# POWR0008_BCR_System.net
KiCad netlist of a schematic drawn in Altium Designer
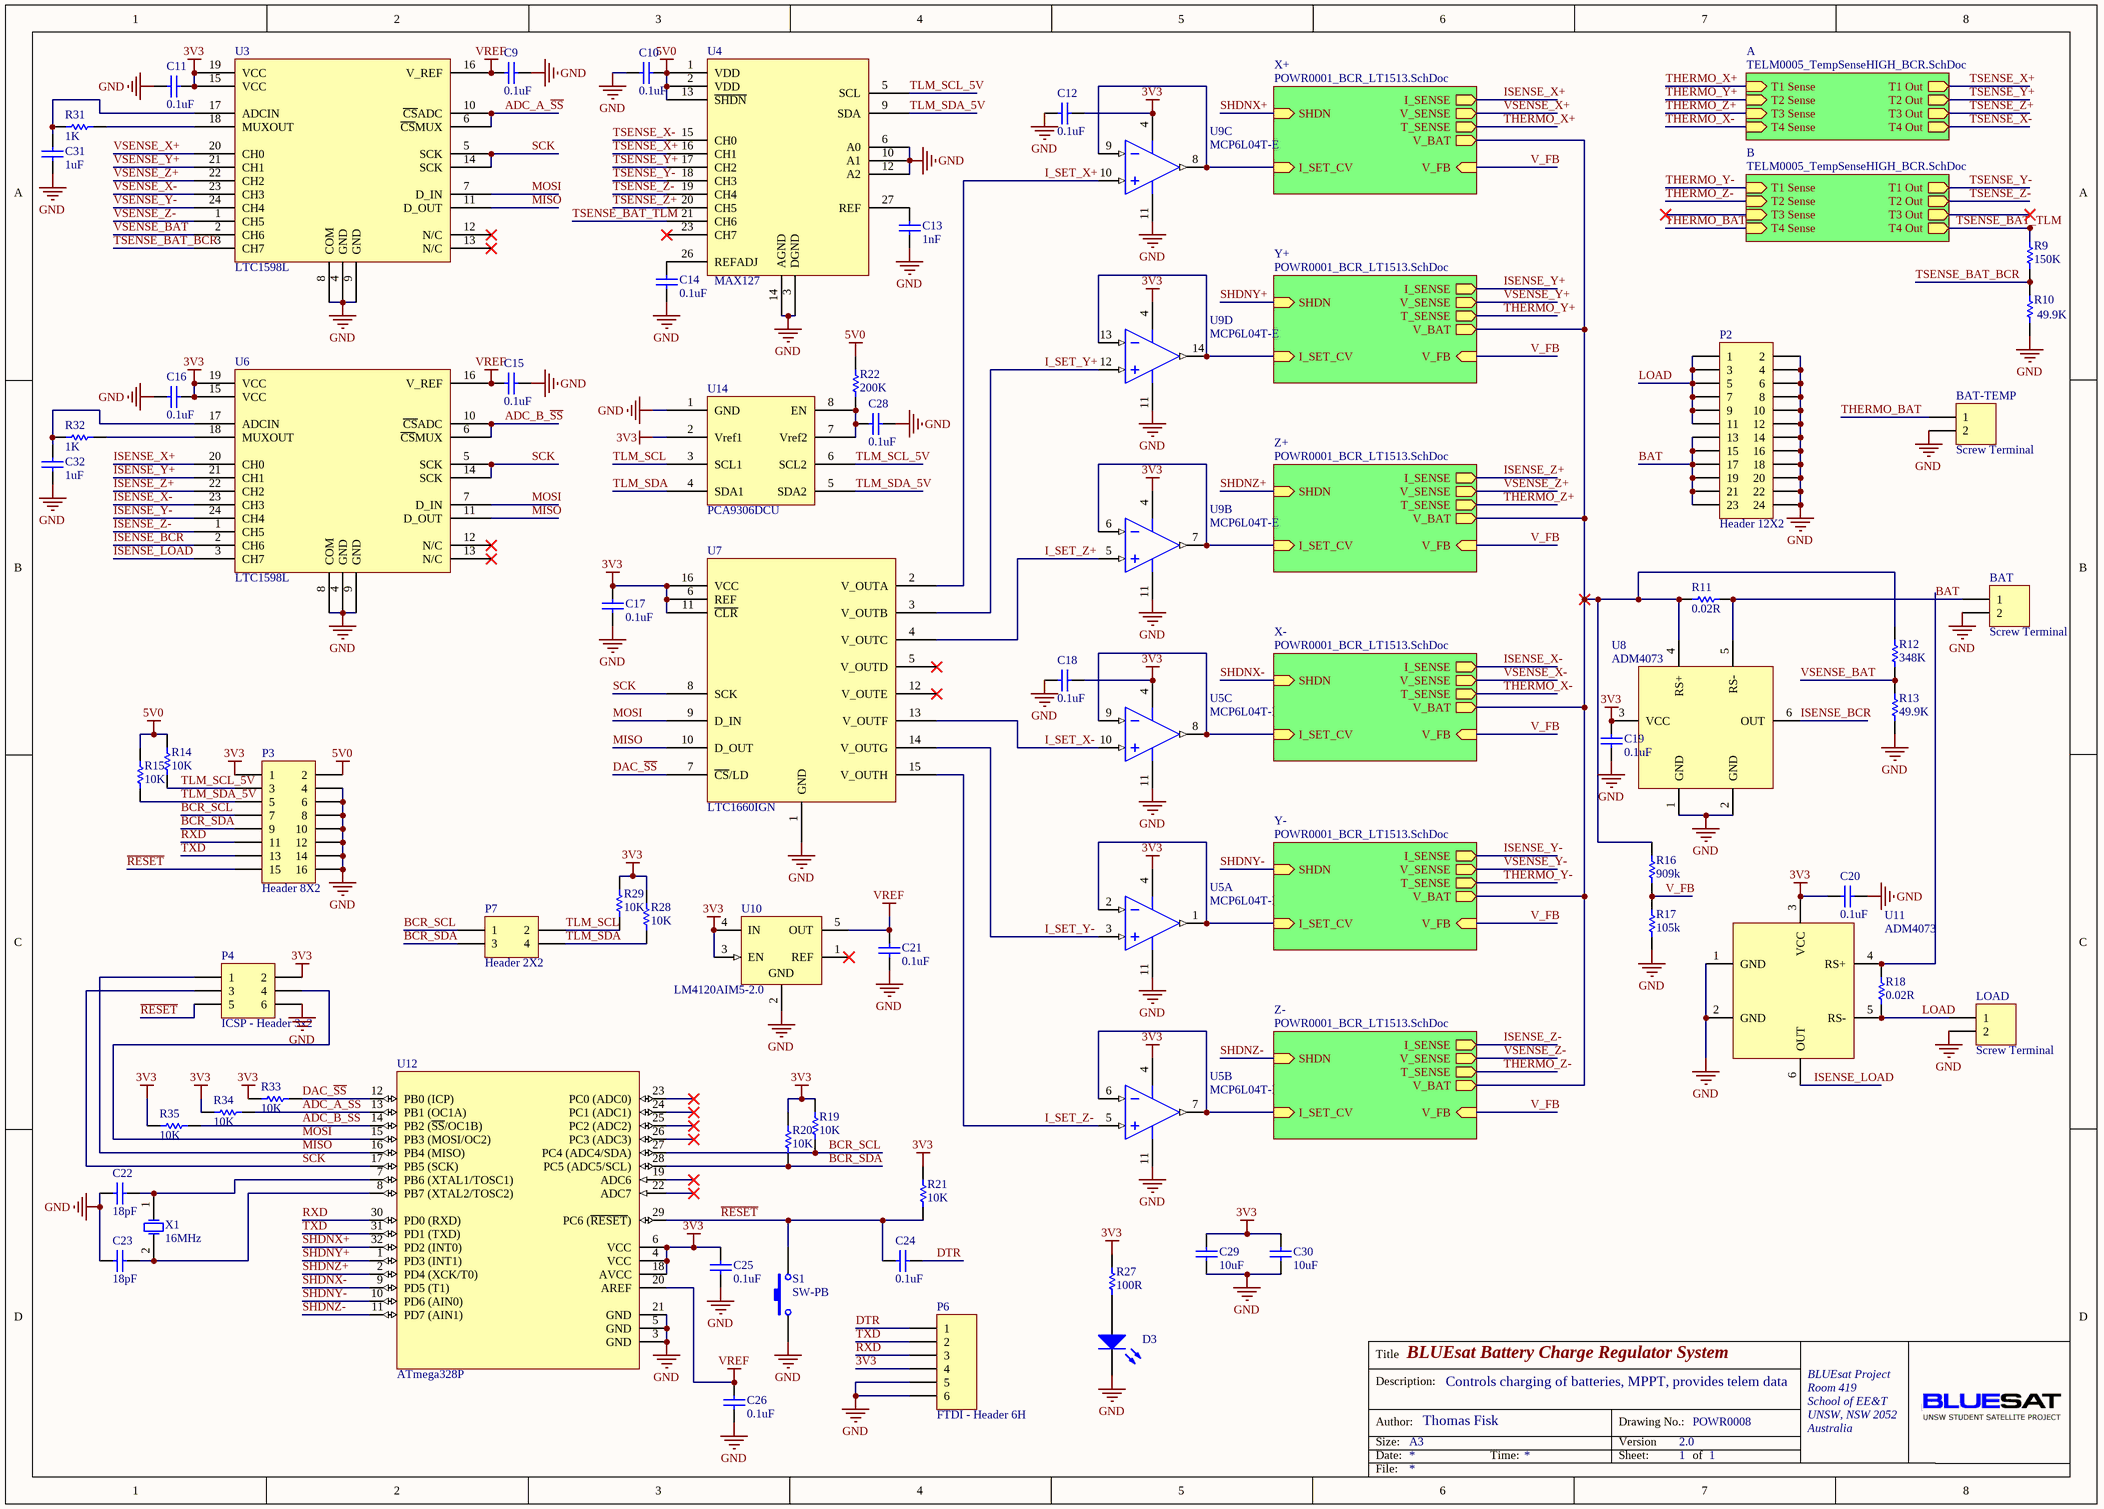
[diagram p0: POWR0008_BCR_System.SchDoc]

(export (version "E")
  (design (tool "Eeschema 10.0.6"))
  (components
    (comp (ref "BAT")
      (value "Screw Terminal")
      (footprint "5.05mm Terminal Block - 2")
      (description "Header, 2-Pin")
      (fields (field (name "PUBLISHER") "Altium Limited"))
      (libsource (lib "Miscellaneous Connectors") (part "Header 2"))
    )
    (comp (ref "BAT-TEMP")
      (value "Screw Terminal")
      (footprint "5.05mm Terminal Block - 2")
      (description "Header, 2-Pin")
      (fields (field (name "PUBLISHER") "Altium Limited"))
      (libsource (lib "Miscellaneous Connectors") (part "Header 2"))
    )
    (comp (ref "C9")
      (value "0.1uF")
      (footprint "CAPC2012M")
      (description "Capacitor")
      (fields (field (name "Comment") "Cap") (field (name "PUBLISHER") "Altium Limited"))
      (libsource (lib "Miscellaneous Devices") (part "Cap"))
    )
    (comp (ref "C10")
      (value "0.1uF")
      (footprint "CAPC2012M")
      (description "Capacitor")
      (fields (field (name "Comment") "Cap") (field (name "PUBLISHER") "Altium Limited"))
      (libsource (lib "Miscellaneous Devices") (part "Cap"))
    )
    (comp (ref "C11")
      (value "0.1uF")
      (footprint "CAPC2012M")
      (description "Capacitor")
      (fields (field (name "Comment") "Cap") (field (name "PUBLISHER") "Altium Limited"))
      (libsource (lib "Miscellaneous Devices") (part "Cap"))
    )
    (comp (ref "C12")
      (value "0.1uF")
      (footprint "CAPC2012M")
      (description "Capacitor")
      (fields (field (name "Comment") "Cap") (field (name "PUBLISHER") "Altium Limited"))
      (libsource (lib "Miscellaneous Devices") (part "Cap"))
    )
    (comp (ref "C13")
      (value "1nF")
      (footprint "CAPC2012M")
      (description "Capacitor")
      (fields (field (name "Comment") "Cap") (field (name "PUBLISHER") "Altium Limited"))
      (libsource (lib "Miscellaneous Devices") (part "Cap"))
    )
    (comp (ref "C14")
      (value "0.1uF")
      (footprint "CAPC2012M")
      (description "Capacitor")
      (fields (field (name "Comment") "Cap") (field (name "PUBLISHER") "Altium Limited"))
      (libsource (lib "Miscellaneous Devices") (part "Cap"))
    )
    (comp (ref "C15")
      (value "0.1uF")
      (footprint "CAPC2012M")
      (description "Capacitor")
      (fields (field (name "Comment") "Cap") (field (name "PUBLISHER") "Altium Limited"))
      (libsource (lib "Miscellaneous Devices") (part "Cap"))
    )
    (comp (ref "C16")
      (value "0.1uF")
      (footprint "CAPC2012M")
      (description "Capacitor")
      (fields (field (name "Comment") "Cap") (field (name "PUBLISHER") "Altium Limited"))
      (libsource (lib "Miscellaneous Devices") (part "Cap"))
    )
    (comp (ref "C17")
      (value "0.1uF")
      (footprint "CAPC2012M")
      (description "Capacitor")
      (fields (field (name "Comment") "Cap") (field (name "PUBLISHER") "Altium Limited"))
      (libsource (lib "Miscellaneous Devices") (part "Cap"))
    )
    (comp (ref "C18")
      (value "0.1uF")
      (footprint "CAPC2012M")
      (description "Capacitor")
      (fields (field (name "Comment") "Cap") (field (name "PUBLISHER") "Altium Limited"))
      (libsource (lib "Miscellaneous Devices") (part "Cap"))
    )
    (comp (ref "C19")
      (value "0.1uF")
      (footprint "CAPC2012M")
      (description "Capacitor")
      (fields (field (name "Comment") "Cap") (field (name "PUBLISHER") "Altium Limited"))
      (libsource (lib "Miscellaneous Devices") (part "Cap"))
    )
    (comp (ref "C20")
      (value "0.1uF")
      (footprint "CAPC2012M")
      (description "Capacitor")
      (fields (field (name "Comment") "Cap") (field (name "PUBLISHER") "Altium Limited"))
      (libsource (lib "Miscellaneous Devices") (part "Cap"))
    )
    (comp (ref "C21")
      (value "0.1uF")
      (footprint "CAPC2012M")
      (description "Capacitor")
      (fields (field (name "Comment") "Cap") (field (name "PUBLISHER") "Altium Limited"))
      (libsource (lib "Miscellaneous Devices") (part "Cap"))
    )
    (comp (ref "C22")
      (value "18pF")
      (footprint "CAPC2012M")
      (description "Capacitor")
      (fields (field (name "Comment") "Cap") (field (name "PUBLISHER") "Altium Limited"))
      (libsource (lib "Miscellaneous Devices") (part "Cap"))
    )
    (comp (ref "C23")
      (value "18pF")
      (footprint "CAPC2012M")
      (description "Capacitor")
      (fields (field (name "Comment") "Cap") (field (name "PUBLISHER") "Altium Limited"))
      (libsource (lib "Miscellaneous Devices") (part "Cap"))
    )
    (comp (ref "C24")
      (value "0.1uF")
      (footprint "CAPC2012M")
      (description "Capacitor")
      (fields (field (name "Comment") "Cap") (field (name "PUBLISHER") "Altium Limited"))
      (libsource (lib "Miscellaneous Devices") (part "Cap"))
    )
    (comp (ref "C25")
      (value "0.1uF")
      (footprint "CAPC2012M")
      (description "Capacitor")
      (fields (field (name "Comment") "Cap") (field (name "PUBLISHER") "Altium Limited"))
      (libsource (lib "Miscellaneous Devices") (part "Cap"))
    )
    (comp (ref "C26")
      (value "0.1uF")
      (footprint "CAPC2012M")
      (description "Capacitor")
      (fields (field (name "Comment") "Cap") (field (name "PUBLISHER") "Altium Limited"))
      (libsource (lib "Miscellaneous Devices") (part "Cap"))
    )
    (comp (ref "C28")
      (value "0.1uF")
      (footprint "CAPC2012M")
      (description "Capacitor")
      (fields (field (name "Comment") "Cap") (field (name "PUBLISHER") "Altium Limited"))
      (libsource (lib "Miscellaneous Devices") (part "Cap"))
    )
    (comp (ref "C29")
      (value "10uF")
      (footprint "CAPC3216M")
      (description "Capacitor")
      (fields (field (name "Comment") "Cap") (field (name "PUBLISHER") "Altium Limited"))
      (libsource (lib "Miscellaneous Devices") (part "Cap"))
    )
    (comp (ref "C30")
      (value "10uF")
      (footprint "CAPC3216M")
      (description "Capacitor")
      (fields (field (name "Comment") "Cap") (field (name "PUBLISHER") "Altium Limited"))
      (libsource (lib "Miscellaneous Devices") (part "Cap"))
    )
    (comp (ref "C31")
      (value "1uF")
      (footprint "CAPC2012M")
      (description "Capacitor")
      (fields (field (name "Comment") "Cap") (field (name "PUBLISHER") "Altium Limited"))
      (libsource (lib "Miscellaneous Devices") (part "Cap"))
    )
    (comp (ref "C32")
      (value "1uF")
      (footprint "CAPC2012M")
      (description "Capacitor")
      (fields (field (name "Comment") "Cap") (field (name "PUBLISHER") "Altium Limited"))
      (libsource (lib "Miscellaneous Devices") (part "Cap"))
    )
    (comp (ref "D3")
      (value "0805 LED")
      (footprint "CD2012-0805")
      (description "Typical RED, GREEN, YELLOW, AMBER GaAs LED")
      (fields (field (name "PUBLISHER") "Altium Limited"))
      (libsource (lib "Miscellaneous Devices") (part "LED2"))
    )
    (comp (ref "LOAD")
      (value "Screw Terminal")
      (footprint "5.05mm Terminal Block - 2")
      (description "Header, 2-Pin")
      (fields (field (name "PUBLISHER") "Altium Limited"))
      (libsource (lib "Miscellaneous Connectors") (part "Header 2"))
    )
    (comp (ref "P2")
      (value "Header 12X2")
      (footprint "HDR2X12")
      (description "Header, 12-Pin, Dual row")
      (fields (field (name "PUBLISHER") "Altium Limited"))
      (libsource (lib "Miscellaneous Connectors") (part "Header 12X2"))
    )
    (comp (ref "P3")
      (value "Header 8X2")
      (footprint "HDR2X8")
      (description "Header, 8-Pin, Dual row")
      (fields (field (name "PUBLISHER") "Altium Limited"))
      (libsource (lib "Miscellaneous Connectors") (part "Header 8X2"))
    )
    (comp (ref "P4")
      (value "ICSP - Header 3x2")
      (footprint "HDR2X3")
      (description "Header, 3-Pin, Dual row")
      (fields (field (name "PUBLISHER") "Altium Limited"))
      (libsource (lib "Miscellaneous Connectors") (part "Header 3X2"))
    )
    (comp (ref "P6")
      (value "FTDI - Header 6H")
      (footprint "HDR1X6H")
      (description "Header, 6-Pin, Right Angle")
      (fields (field (name "PUBLISHER") "Altium Limited"))
      (libsource (lib "Miscellaneous Connectors") (part "Header 6H"))
    )
    (comp (ref "P7")
      (value "Header 2X2")
      (footprint "HDR2X2")
      (description "Header, 2-Pin, Dual row")
      (fields (field (name "PUBLISHER") "Altium Limited"))
      (libsource (lib "Miscellaneous Connectors") (part "Header 2X2"))
    )
    (comp (ref "R9")
      (value "150K")
      (footprint "RESC2012M")
      (description "Resistor")
      (fields (field (name "Comment") "Res1") (field (name "PUBLISHER") "Altium Limited"))
      (libsource (lib "Miscellaneous Devices") (part "Res1"))
    )
    (comp (ref "R10")
      (value "49.9K")
      (footprint "RESC2012M")
      (description "Resistor")
      (fields (field (name "Comment") "Res1") (field (name "PUBLISHER") "Altium Limited"))
      (libsource (lib "Miscellaneous Devices") (part "Res1"))
    )
    (comp (ref "R11")
      (value "0.02R")
      (footprint "RESC2012M")
      (description "Resistor")
      (fields (field (name "Comment") "0805 Resistor") (field (name "PUBLISHER") "Altium Limited"))
      (libsource (lib "Miscellaneous Devices") (part "Res1"))
    )
    (comp (ref "R12")
      (value "348K")
      (footprint "RESC2012M")
      (description "Resistor")
      (fields (field (name "Comment") "Res1") (field (name "PUBLISHER") "Altium Limited"))
      (libsource (lib "Miscellaneous Devices") (part "Res1"))
    )
    (comp (ref "R13")
      (value "49.9K")
      (footprint "RESC2012M")
      (description "Resistor")
      (fields (field (name "Comment") "Res1") (field (name "PUBLISHER") "Altium Limited"))
      (libsource (lib "Miscellaneous Devices") (part "Res1"))
    )
    (comp (ref "R14")
      (value "10K")
      (footprint "RESC2012M")
      (description "Resistor")
      (fields (field (name "Comment") "Res1") (field (name "PUBLISHER") "Altium Limited"))
      (libsource (lib "Miscellaneous Devices") (part "Res1"))
    )
    (comp (ref "R15")
      (value "10K")
      (footprint "RESC2012M")
      (description "Resistor")
      (fields (field (name "Comment") "Res1") (field (name "PUBLISHER") "Altium Limited"))
      (libsource (lib "Miscellaneous Devices") (part "Res1"))
    )
    (comp (ref "R16")
      (value "909k")
      (footprint "RESC2012M")
      (description "Resistor")
      (fields (field (name "Comment") "Res1") (field (name "PUBLISHER") "Altium Limited"))
      (libsource (lib "Miscellaneous Devices") (part "Res1"))
    )
    (comp (ref "R17")
      (value "105k")
      (footprint "RESC2012M")
      (description "Resistor")
      (fields (field (name "Comment") "Res1") (field (name "PUBLISHER") "Altium Limited"))
      (libsource (lib "Miscellaneous Devices") (part "Res1"))
    )
    (comp (ref "R18")
      (value "0.02R")
      (footprint "RESC2012M")
      (description "Resistor")
      (fields (field (name "Comment") "0805 Resistor") (field (name "PUBLISHER") "Altium Limited"))
      (libsource (lib "Miscellaneous Devices") (part "Res1"))
    )
    (comp (ref "R19")
      (value "10K")
      (footprint "RESC2012M")
      (description "Resistor")
      (fields (field (name "Comment") "Res1") (field (name "PUBLISHER") "Altium Limited"))
      (libsource (lib "Miscellaneous Devices") (part "Res1"))
    )
    (comp (ref "R20")
      (value "10K")
      (footprint "RESC2012M")
      (description "Resistor")
      (fields (field (name "Comment") "Res1") (field (name "PUBLISHER") "Altium Limited"))
      (libsource (lib "Miscellaneous Devices") (part "Res1"))
    )
    (comp (ref "R21")
      (value "10K")
      (footprint "RESC2012M")
      (description "Resistor")
      (fields (field (name "Comment") "Res1") (field (name "PUBLISHER") "Altium Limited"))
      (libsource (lib "Miscellaneous Devices") (part "Res1"))
    )
    (comp (ref "R22")
      (value "200K")
      (footprint "RESC2012M")
      (description "Resistor")
      (fields (field (name "Comment") "Res1") (field (name "PUBLISHER") "Altium Limited"))
      (libsource (lib "Miscellaneous Devices") (part "Res1"))
    )
    (comp (ref "R27")
      (value "100R")
      (footprint "RESC2012M")
      (description "Resistor")
      (fields (field (name "Comment") "Res1") (field (name "PUBLISHER") "Altium Limited"))
      (libsource (lib "Miscellaneous Devices") (part "Res1"))
    )
    (comp (ref "R28")
      (value "10K")
      (footprint "RESC2012M")
      (description "Resistor")
      (fields (field (name "Comment") "Res1") (field (name "PUBLISHER") "Altium Limited"))
      (libsource (lib "Miscellaneous Devices") (part "Res1"))
    )
    (comp (ref "R29")
      (value "10K")
      (footprint "RESC2012M")
      (description "Resistor")
      (fields (field (name "Comment") "Res1") (field (name "PUBLISHER") "Altium Limited"))
      (libsource (lib "Miscellaneous Devices") (part "Res1"))
    )
    (comp (ref "R31")
      (value "1K")
      (footprint "RESC2012M")
      (description "Resistor")
      (fields (field (name "Comment") "Res1") (field (name "PUBLISHER") "Altium Limited"))
      (libsource (lib "Miscellaneous Devices") (part "Res1"))
    )
    (comp (ref "R32")
      (value "1K")
      (footprint "RESC2012M")
      (description "Resistor")
      (fields (field (name "Comment") "Res1") (field (name "PUBLISHER") "Altium Limited"))
      (libsource (lib "Miscellaneous Devices") (part "Res1"))
    )
    (comp (ref "R33")
      (value "10K")
      (footprint "RESC2012M")
      (description "Resistor")
      (fields (field (name "Comment") "Res1") (field (name "PUBLISHER") "Altium Limited"))
      (libsource (lib "Miscellaneous Devices") (part "Res1"))
    )
    (comp (ref "R34")
      (value "10K")
      (footprint "RESC2012M")
      (description "Resistor")
      (fields (field (name "Comment") "Res1") (field (name "PUBLISHER") "Altium Limited"))
      (libsource (lib "Miscellaneous Devices") (part "Res1"))
    )
    (comp (ref "R35")
      (value "10K")
      (footprint "RESC2012M")
      (description "Resistor")
      (fields (field (name "Comment") "Res1") (field (name "PUBLISHER") "Altium Limited"))
      (libsource (lib "Miscellaneous Devices") (part "Res1"))
    )
    (comp (ref "S1")
      (value "SW-PB")
      (footprint "RESET SWITCH")
      (description "Switch")
      (fields (field (name "PUBLISHER") "Altium Limited"))
      (libsource (lib "Miscellaneous Devices") (part "SW-PB"))
    )
    (comp (ref "U3") (value "LTC1598L") (footprint "LTC1598L") (libsource (lib "BCR") (part "LTC1598L")))
    (comp (ref "U4")
      (value "MAX127")
      (footprint "SSOP28 - MAX127")
      (description "8 Channel, 12 bit, I2C DAS")
      (libsource (lib "Schlib1") (part "MAX127"))
    )
    (comp (ref "U5")
      (value "MCP6L04T-E")
      (footprint "MTC14_N")
      (description "3 MHz, Micropower RRO Amplifier")
      (fields
        (field (name "PARTNUMBER") "LMV554MT")
        (field (name "MANUFACTURER") "National Semiconductor")
        (field (name "PUBLISHER") "Altium Limited")
      )
      (libsource (lib "NSC Amplifier") (part "LMV554MT"))
    )
    (comp (ref "U6") (value "LTC1598L") (footprint "LTC1598L") (libsource (lib "BCR") (part "LTC1598L")))
    (comp (ref "U7") (value "LTC1660IGN") (footprint "LTC1660") (libsource (lib "BCR") (part "LTC1660IGN")))
    (comp (ref "U8")
      (value "ADM4073")
      (footprint "SOT95P285X145-6N")
      (description "Current Sense Amplifer")
      (libsource (lib "Schlib1") (part "ADM4073"))
    )
    (comp (ref "U9")
      (value "MCP6L04T-E")
      (footprint "MTC14_N")
      (description "3 MHz, Micropower RRO Amplifier")
      (fields
        (field (name "PARTNUMBER") "LMV554MT")
        (field (name "MANUFACTURER") "National Semiconductor")
        (field (name "PUBLISHER") "Altium Limited")
      )
      (libsource (lib "NSC Amplifier") (part "LMV554MT"))
    )
    (comp (ref "U10")
      (value "LM4120AIM5-2.0")
      (footprint "MF05A_N")
      (description "Precision Micropower Low Dropout Voltage Reference")
      (fields
        (field (name "MANUFACTURER") "National Semiconductor")
        (field (name "DIGIKEYPARTNUMBER") "LM4120AIM5-2.0CT-ND")
        (field (name "PUBLISHER") "Altium Limited")
      )
      (libsource (lib "NSC Voltage Reference") (part "LM4120AIM5-2.0"))
    )
    (comp (ref "U11")
      (value "ADM4073")
      (footprint "SOT95P285X145-6N")
      (description "Current Sense Amplifer")
      (libsource (lib "") (part "ADM4073_1"))
    )
    (comp (ref "U12")
      (value "ATmega328P")
      (footprint "32A_N")
      (description "8-Bit AVR Microcontroller with 8K Bytes of In-System Programmable Flash Memory")
      (fields (field (name "PUBLISHER") "Altium Limited"))
      (libsource (lib "Atmel Microcontroller 8-Bit AVR") (part "ATmega8-16AC"))
    )
    (comp (ref "U14")
      (value "PCA9306DCU")
      (footprint "TSSOP50P310X90-8N")
      (libsource (lib "BCR") (part "PCA9306"))
    )
    (comp (ref "X1")
      (value "16MHz")
      (footprint "HC49 - No border")
      (description "Crystal Oscillator")
      (fields (field (name "PUBLISHER") "Altium Limited"))
      (libsource (lib "ECS Crystal Oscillator") (part "ECS-110-S-5P"))
    )
  )
  (nets
    (net (code "1") (name "/ADC_A_~{SS}") (class "Default")
      (node (ref "R34") (pin "2") (pinfunction "2_2") (pintype "passive"))
      (node (ref "U12") (pin "13") (pinfunction "PB1_(OC1A)_13") (pintype "bidirectional"))
      (node (ref "U3") (pin "10") (pinfunction "~{CS}ADC_10") (pintype "passive"))
      (node (ref "U3") (pin "6") (pinfunction "~{CS}MUX_6") (pintype "passive"))
    )
    (net (code "2") (name "/ADC_B_~{SS}") (class "Default")
      (node (ref "R35") (pin "2") (pinfunction "2_2") (pintype "passive"))
      (node (ref "U12") (pin "14") (pinfunction "PB2_(~{SS}/OC1B)_14") (pintype "bidirectional"))
      (node (ref "U6") (pin "10") (pinfunction "~{CS}ADC_10") (pintype "passive"))
      (node (ref "U6") (pin "6") (pinfunction "~{CS}MUX_6") (pintype "passive"))
    )
    (net (code "3") (name "/BAT") (class "Default")
      (node (ref "BAT") (pin "1") (pinfunction "1_1") (pintype "passive"))
      (node (ref "P2") (pin "13") (pinfunction "13_13") (pintype "passive"))
      (node (ref "P2") (pin "15") (pinfunction "15_15") (pintype "passive"))
      (node (ref "P2") (pin "17") (pinfunction "17_17") (pintype "passive"))
      (node (ref "P2") (pin "19") (pinfunction "19_19") (pintype "passive"))
      (node (ref "P2") (pin "21") (pinfunction "21_21") (pintype "passive"))
      (node (ref "P2") (pin "23") (pinfunction "23_23") (pintype "passive"))
      (node (ref "R11") (pin "2") (pinfunction "2_2") (pintype "passive"))
      (node (ref "R18") (pin "2") (pinfunction "2_2") (pintype "passive"))
      (node (ref "U11") (pin "4") (pinfunction "RS+_4") (pintype "passive"))
      (node (ref "U8") (pin "5") (pinfunction "RS-_5") (pintype "passive"))
    )
    (net (code "4") (name "/BCR_SCL") (class "Default")
      (node (ref "P3") (pin "7") (pinfunction "7_7") (pintype "passive"))
      (node (ref "P7") (pin "1") (pinfunction "1_1") (pintype "passive"))
      (node (ref "R19") (pin "2") (pinfunction "2_2") (pintype "passive"))
      (node (ref "U12") (pin "27") (pinfunction "PC4_(ADC4/SDA)_27") (pintype "bidirectional"))
    )
    (net (code "5") (name "/BCR_SDA") (class "Default")
      (node (ref "P3") (pin "9") (pinfunction "9_9") (pintype "passive"))
      (node (ref "P7") (pin "3") (pinfunction "3_3") (pintype "passive"))
      (node (ref "R20") (pin "2") (pinfunction "2_2") (pintype "passive"))
      (node (ref "U12") (pin "28") (pinfunction "PC5_(ADC5/SCL)_28") (pintype "bidirectional"))
    )
    (net (code "6") (name "/DAC_~{SS}") (class "Default")
      (node (ref "R33") (pin "2") (pinfunction "2_2") (pintype "passive"))
      (node (ref "U12") (pin "12") (pinfunction "PB0_(ICP)_12") (pintype "bidirectional"))
      (node (ref "U7") (pin "7") (pinfunction "~{CS}/LD_7") (pintype "passive"))
    )
    (net (code "7") (name "/DTR") (class "Default")
      (node (ref "C24") (pin "1") (pinfunction "1_1") (pintype "passive"))
      (node (ref "P6") (pin "1") (pinfunction "1_1") (pintype "passive"))
    )
    (net (code "8") (name "/ISENSE_BCR") (class "Default")
      (node (ref "U6") (pin "2") (pinfunction "CH6_2") (pintype "passive"))
      (node (ref "U8") (pin "6") (pinfunction "OUT_6") (pintype "passive"))
    )
    (net (code "9") (name "/ISENSE_LOAD") (class "Default")
      (node (ref "U11") (pin "6") (pinfunction "OUT_6") (pintype "passive"))
      (node (ref "U6") (pin "3") (pinfunction "CH7_3") (pintype "passive"))
    )
    (net (code "10") (name "/ISENSE_X+") (class "Default")
      (node (ref "U6") (pin "20") (pinfunction "CH0_20") (pintype "passive"))
    )
    (net (code "11") (name "/ISENSE_X-") (class "Default")
      (node (ref "U6") (pin "23") (pinfunction "CH3_23") (pintype "passive"))
    )
    (net (code "12") (name "/ISENSE_Y+") (class "Default")
      (node (ref "U6") (pin "21") (pinfunction "CH1_21") (pintype "passive"))
    )
    (net (code "13") (name "/ISENSE_Y-") (class "Default")
      (node (ref "U6") (pin "24") (pinfunction "CH4_24") (pintype "passive"))
    )
    (net (code "14") (name "/ISENSE_Z+") (class "Default")
      (node (ref "U6") (pin "22") (pinfunction "CH2_22") (pintype "passive"))
    )
    (net (code "15") (name "/ISENSE_Z-") (class "Default")
      (node (ref "U6") (pin "1") (pinfunction "CH5_1") (pintype "passive"))
    )
    (net (code "16") (name "/I_SET_CV") (class "Default")
      (node (ref "U5") (pin "6") (pinfunction "INB-_6") (pintype "input"))
      (node (ref "U5") (pin "7") (pinfunction "OUTB_7") (pintype "output"))
    )
    (net (code "17") (name "/I_SET_CV_1") (class "Default")
      (node (ref "U5") (pin "8") (pinfunction "OUTC_8") (pintype "output"))
      (node (ref "U5") (pin "9") (pinfunction "INC-_9") (pintype "input"))
    )
    (net (code "18") (name "/I_SET_CV_2") (class "Default")
      (node (ref "U9") (pin "13") (pinfunction "IND-_13") (pintype "input"))
      (node (ref "U9") (pin "14") (pinfunction "OUTD_14") (pintype "output"))
    )
    (net (code "19") (name "/I_SET_CV_3") (class "Default")
      (node (ref "U9") (pin "8") (pinfunction "OUTC_8") (pintype "output"))
      (node (ref "U9") (pin "9") (pinfunction "INC-_9") (pintype "input"))
    )
    (net (code "20") (name "/I_SET_CV_4") (class "Default")
      (node (ref "U9") (pin "6") (pinfunction "INB-_6") (pintype "input"))
      (node (ref "U9") (pin "7") (pinfunction "OUTB_7") (pintype "output"))
    )
    (net (code "21") (name "/I_SET_CV_5") (class "Default")
      (node (ref "U5") (pin "1") (pinfunction "OUTA_1") (pintype "output"))
      (node (ref "U5") (pin "2") (pinfunction "INA-_2") (pintype "input"))
    )
    (net (code "22") (name "/I_SET_X+") (class "Default")
      (node (ref "U7") (pin "2") (pinfunction "V_OUTA_2") (pintype "passive"))
      (node (ref "U9") (pin "10") (pinfunction "INC+_10") (pintype "input"))
    )
    (net (code "23") (name "/I_SET_X-") (class "Default")
      (node (ref "U5") (pin "10") (pinfunction "INC+_10") (pintype "input"))
      (node (ref "U7") (pin "13") (pinfunction "V_OUTF_13") (pintype "passive"))
    )
    (net (code "24") (name "/I_SET_Y+") (class "Default")
      (node (ref "U7") (pin "3") (pinfunction "V_OUTB_3") (pintype "passive"))
      (node (ref "U9") (pin "12") (pinfunction "IND+_12") (pintype "input"))
    )
    (net (code "25") (name "/I_SET_Y-") (class "Default")
      (node (ref "U5") (pin "3") (pinfunction "INA+_3") (pintype "input"))
      (node (ref "U7") (pin "14") (pinfunction "V_OUTG_14") (pintype "passive"))
    )
    (net (code "26") (name "/I_SET_Z+") (class "Default")
      (node (ref "U7") (pin "4") (pinfunction "V_OUTC_4") (pintype "passive"))
      (node (ref "U9") (pin "5") (pinfunction "INB+_5") (pintype "input"))
    )
    (net (code "27") (name "/I_SET_Z-") (class "Default")
      (node (ref "U5") (pin "5") (pinfunction "INB+_5") (pintype "input"))
      (node (ref "U7") (pin "15") (pinfunction "V_OUTH_15") (pintype "passive"))
    )
    (net (code "28") (name "/LOAD") (class "Default")
      (node (ref "LOAD") (pin "1") (pinfunction "1_1") (pintype "passive"))
      (node (ref "P2") (pin "1") (pinfunction "1_1") (pintype "passive"))
      (node (ref "P2") (pin "11") (pinfunction "11_11") (pintype "passive"))
      (node (ref "P2") (pin "3") (pinfunction "3_3") (pintype "passive"))
      (node (ref "P2") (pin "5") (pinfunction "5_5") (pintype "passive"))
      (node (ref "P2") (pin "7") (pinfunction "7_7") (pintype "passive"))
      (node (ref "P2") (pin "9") (pinfunction "9_9") (pintype "passive"))
      (node (ref "R18") (pin "1") (pinfunction "1_1") (pintype "passive"))
      (node (ref "U11") (pin "5") (pinfunction "RS-_5") (pintype "passive"))
    )
    (net (code "29") (name "/MISO") (class "Default")
      (node (ref "P4") (pin "1") (pinfunction "1_1") (pintype "passive"))
      (node (ref "U12") (pin "16") (pinfunction "PB4_(MISO)_16") (pintype "bidirectional"))
      (node (ref "U3") (pin "11") (pinfunction "D_OUT_11") (pintype "passive"))
      (node (ref "U6") (pin "11") (pinfunction "D_OUT_11") (pintype "passive"))
      (node (ref "U7") (pin "10") (pinfunction "D_OUT_10") (pintype "passive"))
    )
    (net (code "30") (name "/MOSI") (class "Default")
      (node (ref "P4") (pin "4") (pinfunction "4_4") (pintype "passive"))
      (node (ref "U12") (pin "15") (pinfunction "PB3_(MOSI/OC2)_15") (pintype "bidirectional"))
      (node (ref "U3") (pin "7") (pinfunction "D_IN_7") (pintype "passive"))
      (node (ref "U6") (pin "7") (pinfunction "D_IN_7") (pintype "passive"))
      (node (ref "U7") (pin "9") (pinfunction "D_IN_9") (pintype "passive"))
    )
    (net (code "31") (name "/RXD") (class "Default")
      (node (ref "P3") (pin "11") (pinfunction "11_11") (pintype "passive"))
      (node (ref "P6") (pin "3") (pinfunction "3_3") (pintype "passive"))
      (node (ref "U12") (pin "30") (pinfunction "PD0_(RXD)_30") (pintype "bidirectional"))
    )
    (net (code "32") (name "/SCK") (class "Default")
      (node (ref "P4") (pin "3") (pinfunction "3_3") (pintype "passive"))
      (node (ref "U12") (pin "17") (pinfunction "PB5_(SCK)_17") (pintype "bidirectional"))
      (node (ref "U3") (pin "14") (pinfunction "SCK_14") (pintype "passive"))
      (node (ref "U3") (pin "5") (pinfunction "SCK_5") (pintype "passive"))
      (node (ref "U6") (pin "14") (pinfunction "SCK_14") (pintype "passive"))
      (node (ref "U6") (pin "5") (pinfunction "SCK_5") (pintype "passive"))
      (node (ref "U7") (pin "8") (pinfunction "SCK_8") (pintype "passive"))
    )
    (net (code "33") (name "/SHDNX+") (class "Default")
      (node (ref "U12") (pin "32") (pinfunction "PD2_(INT0)_32") (pintype "bidirectional"))
    )
    (net (code "34") (name "/SHDNX-") (class "Default")
      (node (ref "U12") (pin "9") (pinfunction "PD5_(T1)_9") (pintype "bidirectional"))
    )
    (net (code "35") (name "/SHDNY+") (class "Default")
      (node (ref "U12") (pin "1") (pinfunction "PD3_(INT1)_1") (pintype "bidirectional"))
    )
    (net (code "36") (name "/SHDNY-") (class "Default")
      (node (ref "U12") (pin "10") (pinfunction "PD6_(AIN0)_10") (pintype "bidirectional"))
    )
    (net (code "37") (name "/SHDNZ+") (class "Default")
      (node (ref "U12") (pin "2") (pinfunction "PD4_(XCK/T0)_2") (pintype "bidirectional"))
    )
    (net (code "38") (name "/SHDNZ-") (class "Default")
      (node (ref "U12") (pin "11") (pinfunction "PD7_(AIN1)_11") (pintype "bidirectional"))
    )
    (net (code "41") (name "/THERMO_BAT") (class "Default")
      (node (ref "BAT-TEMP") (pin "1") (pinfunction "1_1") (pintype "passive"))
    )
    (net (code "48") (name "/TLM_SCL") (class "Default")
      (node (ref "P7") (pin "2") (pinfunction "2_2") (pintype "passive"))
      (node (ref "R29") (pin "1") (pinfunction "1_1") (pintype "passive"))
      (node (ref "U14") (pin "3") (pinfunction "SCL1_3") (pintype "passive"))
    )
    (net (code "49") (name "/TLM_SCL_5V") (class "Default")
      (node (ref "P3") (pin "3") (pinfunction "3_3") (pintype "passive"))
      (node (ref "R14") (pin "2") (pinfunction "2_2") (pintype "passive"))
      (node (ref "U14") (pin "6") (pinfunction "SCL2_6") (pintype "passive"))
      (node (ref "U4") (pin "5") (pinfunction "SCL_5") (pintype "passive"))
    )
    (net (code "50") (name "/TLM_SDA") (class "Default")
      (node (ref "P7") (pin "4") (pinfunction "4_4") (pintype "passive"))
      (node (ref "R28") (pin "1") (pinfunction "1_1") (pintype "passive"))
      (node (ref "U14") (pin "4") (pinfunction "SDA1_4") (pintype "passive"))
    )
    (net (code "51") (name "/TLM_SDA_5V") (class "Default")
      (node (ref "P3") (pin "5") (pinfunction "5_5") (pintype "passive"))
      (node (ref "R15") (pin "2") (pinfunction "2_2") (pintype "passive"))
      (node (ref "U14") (pin "5") (pinfunction "SDA2_5") (pintype "passive"))
      (node (ref "U4") (pin "9") (pinfunction "SDA_9") (pintype "passive"))
    )
    (net (code "52") (name "/TSENSE_BAT_BCR") (class "Default")
      (node (ref "R10") (pin "1") (pinfunction "1_1") (pintype "passive"))
      (node (ref "R9") (pin "1") (pinfunction "1_1") (pintype "passive"))
      (node (ref "U3") (pin "3") (pinfunction "CH7_3") (pintype "passive"))
    )
    (net (code "53") (name "/TSENSE_BAT_TLM") (class "Default")
      (node (ref "R9") (pin "2") (pinfunction "2_2") (pintype "passive"))
      (node (ref "U4") (pin "21") (pinfunction "CH6_21") (pintype "passive"))
    )
    (net (code "54") (name "/TSENSE_X+") (class "Default")
      (node (ref "U4") (pin "16") (pinfunction "CH1_16") (pintype "passive"))
    )
    (net (code "55") (name "/TSENSE_X-") (class "Default")
      (node (ref "U4") (pin "15") (pinfunction "CH0_15") (pintype "passive"))
    )
    (net (code "56") (name "/TSENSE_Y+") (class "Default")
      (node (ref "U4") (pin "17") (pinfunction "CH2_17") (pintype "passive"))
    )
    (net (code "57") (name "/TSENSE_Y-") (class "Default")
      (node (ref "U4") (pin "18") (pinfunction "CH3_18") (pintype "passive"))
    )
    (net (code "58") (name "/TSENSE_Z+") (class "Default")
      (node (ref "U4") (pin "20") (pinfunction "CH5_20") (pintype "passive"))
    )
    (net (code "59") (name "/TSENSE_Z-") (class "Default")
      (node (ref "U4") (pin "19") (pinfunction "CH4_19") (pintype "passive"))
    )
    (net (code "60") (name "/TXD") (class "Default")
      (node (ref "P3") (pin "13") (pinfunction "13_13") (pintype "passive"))
      (node (ref "P6") (pin "2") (pinfunction "2_2") (pintype "passive"))
      (node (ref "U12") (pin "31") (pinfunction "PD1_(TXD)_31") (pintype "bidirectional"))
    )
    (net (code "61") (name "/VSENSE_BAT") (class "Default")
      (node (ref "R12") (pin "2") (pinfunction "2_2") (pintype "passive"))
      (node (ref "R13") (pin "1") (pinfunction "1_1") (pintype "passive"))
      (node (ref "U3") (pin "2") (pinfunction "CH6_2") (pintype "passive"))
    )
    (net (code "62") (name "/VSENSE_X+") (class "Default")
      (node (ref "U3") (pin "20") (pinfunction "CH0_20") (pintype "passive"))
    )
    (net (code "63") (name "/VSENSE_X-") (class "Default")
      (node (ref "U3") (pin "23") (pinfunction "CH3_23") (pintype "passive"))
    )
    (net (code "64") (name "/VSENSE_Y+") (class "Default")
      (node (ref "U3") (pin "21") (pinfunction "CH1_21") (pintype "passive"))
    )
    (net (code "65") (name "/VSENSE_Y-") (class "Default")
      (node (ref "U3") (pin "24") (pinfunction "CH4_24") (pintype "passive"))
    )
    (net (code "66") (name "/VSENSE_Z+") (class "Default")
      (node (ref "U3") (pin "22") (pinfunction "CH2_22") (pintype "passive"))
    )
    (net (code "67") (name "/VSENSE_Z-") (class "Default")
      (node (ref "U3") (pin "1") (pinfunction "CH5_1") (pintype "passive"))
    )
    (net (code "68") (name "/V_BAT") (class "Default")
      (node (ref "R11") (pin "1") (pinfunction "1_1") (pintype "passive"))
      (node (ref "R12") (pin "1") (pinfunction "1_1") (pintype "passive"))
      (node (ref "R16") (pin "2") (pinfunction "2_2") (pintype "passive"))
      (node (ref "U8") (pin "4") (pinfunction "RS+_4") (pintype "passive"))
    )
    (net (code "69") (name "/V_FB") (class "Default")
      (node (ref "R16") (pin "1") (pinfunction "1_1") (pintype "passive"))
      (node (ref "R17") (pin "2") (pinfunction "2_2") (pintype "passive"))
    )
    (net (code "70") (name "/~{RESET}") (class "Default")
      (node (ref "C24") (pin "2") (pinfunction "2_2") (pintype "passive"))
      (node (ref "P3") (pin "15") (pinfunction "15_15") (pintype "passive"))
      (node (ref "P4") (pin "5") (pinfunction "5_5") (pintype "passive"))
      (node (ref "R21") (pin "2") (pinfunction "2_2") (pintype "passive"))
      (node (ref "S1") (pin "2") (pinfunction "2_2") (pintype "passive"))
      (node (ref "U12") (pin "29") (pinfunction "PC6_(~{RESET})_29") (pintype "bidirectional"))
    )
    (net (code "71") (name "3V3") (class "Default")
      (node (ref "C11") (pin "2") (pinfunction "2_2") (pintype "passive"))
      (node (ref "C12") (pin "2") (pinfunction "2_2") (pintype "passive"))
      (node (ref "C16") (pin "2") (pinfunction "2_2") (pintype "passive"))
      (node (ref "C17") (pin "2") (pinfunction "2_2") (pintype "passive"))
      (node (ref "C18") (pin "2") (pinfunction "2_2") (pintype "passive"))
      (node (ref "C19") (pin "1") (pinfunction "1_1") (pintype "passive"))
      (node (ref "C20") (pin "1") (pinfunction "1_1") (pintype "passive"))
      (node (ref "C25") (pin "2") (pinfunction "2_2") (pintype "passive"))
      (node (ref "C29") (pin "2") (pinfunction "2_2") (pintype "passive"))
      (node (ref "C30") (pin "2") (pinfunction "2_2") (pintype "passive"))
      (node (ref "P3") (pin "1") (pinfunction "1_1") (pintype "passive"))
      (node (ref "P4") (pin "2") (pinfunction "2_2") (pintype "passive"))
      (node (ref "P6") (pin "4") (pinfunction "4_4") (pintype "passive"))
      (node (ref "R19") (pin "1") (pinfunction "1_1") (pintype "passive"))
      (node (ref "R20") (pin "1") (pinfunction "1_1") (pintype "passive"))
      (node (ref "R21") (pin "1") (pinfunction "1_1") (pintype "passive"))
      (node (ref "R27") (pin "1") (pinfunction "1_1") (pintype "passive"))
      (node (ref "R28") (pin "2") (pinfunction "2_2") (pintype "passive"))
      (node (ref "R29") (pin "2") (pinfunction "2_2") (pintype "passive"))
      (node (ref "R33") (pin "1") (pinfunction "1_1") (pintype "passive"))
      (node (ref "R34") (pin "1") (pinfunction "1_1") (pintype "passive"))
      (node (ref "R35") (pin "1") (pinfunction "1_1") (pintype "passive"))
      (node (ref "U10") (pin "3") (pinfunction "EN_3") (pintype "input"))
      (node (ref "U10") (pin "4") (pinfunction "IN_4") (pintype "power_in"))
      (node (ref "U11") (pin "3") (pinfunction "VCC_3") (pintype "passive"))
      (node (ref "U12") (pin "18") (pinfunction "AVCC_18") (pintype "power_in"))
      (node (ref "U12") (pin "4") (pinfunction "VCC_4") (pintype "power_in"))
      (node (ref "U12") (pin "6") (pinfunction "VCC_6") (pintype "power_in"))
      (node (ref "U14") (pin "2") (pinfunction "Vref1_2") (pintype "passive"))
      (node (ref "U3") (pin "15") (pinfunction "VCC_15") (pintype "passive"))
      (node (ref "U3") (pin "19") (pinfunction "VCC_19") (pintype "passive"))
      (node (ref "U5") (pin "4") (pinfunction "V+_4") (pintype "power_in"))
      (node (ref "U6") (pin "15") (pinfunction "VCC_15") (pintype "passive"))
      (node (ref "U6") (pin "19") (pinfunction "VCC_19") (pintype "passive"))
      (node (ref "U7") (pin "11") (pinfunction "~{CLR}_11") (pintype "passive"))
      (node (ref "U7") (pin "16") (pinfunction "VCC_16") (pintype "passive"))
      (node (ref "U7") (pin "6") (pinfunction "REF_6") (pintype "passive"))
      (node (ref "U8") (pin "3") (pinfunction "VCC_3") (pintype "passive"))
      (node (ref "U9") (pin "4") (pinfunction "V+_4") (pintype "power_in"))
    )
    (net (code "72") (name "5V0") (class "Default")
      (node (ref "C10") (pin "2") (pinfunction "2_2") (pintype "passive"))
      (node (ref "P3") (pin "2") (pinfunction "2_2") (pintype "passive"))
      (node (ref "R14") (pin "1") (pinfunction "1_1") (pintype "passive"))
      (node (ref "R15") (pin "1") (pinfunction "1_1") (pintype "passive"))
      (node (ref "R22") (pin "1") (pinfunction "1_1") (pintype "passive"))
      (node (ref "U4") (pin "1") (pinfunction "VDD_1") (pintype "passive"))
      (node (ref "U4") (pin "13") (pinfunction "~{SHDN}_13") (pintype "passive"))
      (node (ref "U4") (pin "2") (pinfunction "VDD_2") (pintype "passive"))
    )
    (net (code "73") (name "GND") (class "Default")
      (node (ref "BAT") (pin "2") (pinfunction "2_2") (pintype "passive"))
      (node (ref "BAT-TEMP") (pin "2") (pinfunction "2_2") (pintype "passive"))
      (node (ref "C10") (pin "1") (pinfunction "1_1") (pintype "passive"))
      (node (ref "C11") (pin "1") (pinfunction "1_1") (pintype "passive"))
      (node (ref "C12") (pin "1") (pinfunction "1_1") (pintype "passive"))
      (node (ref "C13") (pin "2") (pinfunction "2_2") (pintype "passive"))
      (node (ref "C14") (pin "1") (pinfunction "1_1") (pintype "passive"))
      (node (ref "C15") (pin "1") (pinfunction "1_1") (pintype "passive"))
      (node (ref "C16") (pin "1") (pinfunction "1_1") (pintype "passive"))
      (node (ref "C17") (pin "1") (pinfunction "1_1") (pintype "passive"))
      (node (ref "C18") (pin "1") (pinfunction "1_1") (pintype "passive"))
      (node (ref "C19") (pin "2") (pinfunction "2_2") (pintype "passive"))
      (node (ref "C20") (pin "2") (pinfunction "2_2") (pintype "passive"))
      (node (ref "C21") (pin "1") (pinfunction "1_1") (pintype "passive"))
      (node (ref "C22") (pin "1") (pinfunction "1_1") (pintype "passive"))
      (node (ref "C23") (pin "1") (pinfunction "1_1") (pintype "passive"))
      (node (ref "C25") (pin "1") (pinfunction "1_1") (pintype "passive"))
      (node (ref "C26") (pin "2") (pinfunction "2_2") (pintype "passive"))
      (node (ref "C28") (pin "1") (pinfunction "1_1") (pintype "passive"))
      (node (ref "C29") (pin "1") (pinfunction "1_1") (pintype "passive"))
      (node (ref "C30") (pin "1") (pinfunction "1_1") (pintype "passive"))
      (node (ref "C31") (pin "1") (pinfunction "1_1") (pintype "passive"))
      (node (ref "C32") (pin "1") (pinfunction "1_1") (pintype "passive"))
      (node (ref "C9") (pin "1") (pinfunction "1_1") (pintype "passive"))
      (node (ref "D3") (pin "2") (pinfunction "K_2") (pintype "passive"))
      (node (ref "LOAD") (pin "2") (pinfunction "2_2") (pintype "passive"))
      (node (ref "P2") (pin "10") (pinfunction "10_10") (pintype "passive"))
      (node (ref "P2") (pin "12") (pinfunction "12_12") (pintype "passive"))
      (node (ref "P2") (pin "14") (pinfunction "14_14") (pintype "passive"))
      (node (ref "P2") (pin "16") (pinfunction "16_16") (pintype "passive"))
      (node (ref "P2") (pin "18") (pinfunction "18_18") (pintype "passive"))
      (node (ref "P2") (pin "2") (pinfunction "2_2") (pintype "passive"))
      (node (ref "P2") (pin "20") (pinfunction "20_20") (pintype "passive"))
      (node (ref "P2") (pin "22") (pinfunction "22_22") (pintype "passive"))
      (node (ref "P2") (pin "24") (pinfunction "24_24") (pintype "passive"))
      (node (ref "P2") (pin "4") (pinfunction "4_4") (pintype "passive"))
      (node (ref "P2") (pin "6") (pinfunction "6_6") (pintype "passive"))
      (node (ref "P2") (pin "8") (pinfunction "8_8") (pintype "passive"))
      (node (ref "P3") (pin "10") (pinfunction "10_10") (pintype "passive"))
      (node (ref "P3") (pin "12") (pinfunction "12_12") (pintype "passive"))
      (node (ref "P3") (pin "14") (pinfunction "14_14") (pintype "passive"))
      (node (ref "P3") (pin "16") (pinfunction "16_16") (pintype "passive"))
      (node (ref "P3") (pin "4") (pinfunction "4_4") (pintype "passive"))
      (node (ref "P3") (pin "6") (pinfunction "6_6") (pintype "passive"))
      (node (ref "P3") (pin "8") (pinfunction "8_8") (pintype "passive"))
      (node (ref "P4") (pin "6") (pinfunction "6_6") (pintype "passive"))
      (node (ref "P6") (pin "5") (pinfunction "5_5") (pintype "passive"))
      (node (ref "P6") (pin "6") (pinfunction "6_6") (pintype "passive"))
      (node (ref "R10") (pin "2") (pinfunction "2_2") (pintype "passive"))
      (node (ref "R13") (pin "2") (pinfunction "2_2") (pintype "passive"))
      (node (ref "R17") (pin "1") (pinfunction "1_1") (pintype "passive"))
      (node (ref "S1") (pin "1") (pinfunction "1_1") (pintype "passive"))
      (node (ref "U10") (pin "2") (pinfunction "GND_2") (pintype "power_in"))
      (node (ref "U11") (pin "1") (pinfunction "GND_1") (pintype "passive"))
      (node (ref "U11") (pin "2") (pinfunction "GND_2") (pintype "passive"))
      (node (ref "U12") (pin "21") (pinfunction "GND_21") (pintype "power_in"))
      (node (ref "U12") (pin "3") (pinfunction "GND_3") (pintype "power_in"))
      (node (ref "U12") (pin "5") (pinfunction "GND_5") (pintype "power_in"))
      (node (ref "U14") (pin "1") (pinfunction "GND_1") (pintype "passive"))
      (node (ref "U3") (pin "4") (pinfunction "GND_4") (pintype "passive"))
      (node (ref "U3") (pin "8") (pinfunction "COM_8") (pintype "passive"))
      (node (ref "U3") (pin "9") (pinfunction "GND_9") (pintype "passive"))
      (node (ref "U4") (pin "10") (pinfunction "A1_10") (pintype "passive"))
      (node (ref "U4") (pin "12") (pinfunction "A2_12") (pintype "passive"))
      (node (ref "U4") (pin "14") (pinfunction "AGND_14") (pintype "passive"))
      (node (ref "U4") (pin "3") (pinfunction "DGND_3") (pintype "passive"))
      (node (ref "U4") (pin "6") (pinfunction "A0_6") (pintype "passive"))
      (node (ref "U5") (pin "11") (pinfunction "V-_11") (pintype "power_in"))
      (node (ref "U6") (pin "4") (pinfunction "GND_4") (pintype "passive"))
      (node (ref "U6") (pin "8") (pinfunction "COM_8") (pintype "passive"))
      (node (ref "U6") (pin "9") (pinfunction "GND_9") (pintype "passive"))
      (node (ref "U7") (pin "1") (pinfunction "GND_1") (pintype "passive"))
      (node (ref "U8") (pin "1") (pinfunction "GND_1") (pintype "passive"))
      (node (ref "U8") (pin "2") (pinfunction "GND_2") (pintype "passive"))
      (node (ref "U9") (pin "11") (pinfunction "V-_11") (pintype "power_in"))
    )
    (net (code "74") (name "Net-(D3-A)") (class "Default")
      (node (ref "D3") (pin "1") (pinfunction "A_1") (pintype "passive"))
      (node (ref "R27") (pin "2") (pinfunction "2_2") (pintype "passive"))
    )
    (net (code "75") (name "Net-(U3-ADCIN)") (class "Default")
      (node (ref "C31") (pin "2") (pinfunction "2_2") (pintype "passive"))
      (node (ref "R31") (pin "2") (pinfunction "2_2") (pintype "passive"))
      (node (ref "U3") (pin "17") (pinfunction "ADCIN_17") (pintype "passive"))
    )
    (net (code "76") (name "Net-(U3-MUXOUT)") (class "Default")
      (node (ref "R31") (pin "1") (pinfunction "1_1") (pintype "passive"))
      (node (ref "U3") (pin "18") (pinfunction "MUXOUT_18") (pintype "passive"))
    )
    (net (code "77") (name "Net-(U4-REF)") (class "Default")
      (node (ref "C13") (pin "1") (pinfunction "1_1") (pintype "passive"))
      (node (ref "U4") (pin "27") (pinfunction "REF_27") (pintype "passive"))
    )
    (net (code "78") (name "Net-(U4-REFADJ)") (class "Default")
      (node (ref "C14") (pin "2") (pinfunction "2_2") (pintype "passive"))
      (node (ref "U4") (pin "26") (pinfunction "REFADJ_26") (pintype "passive"))
    )
    (net (code "79") (name "Net-(U6-ADCIN)") (class "Default")
      (node (ref "C32") (pin "2") (pinfunction "2_2") (pintype "passive"))
      (node (ref "R32") (pin "2") (pinfunction "2_2") (pintype "passive"))
      (node (ref "U6") (pin "17") (pinfunction "ADCIN_17") (pintype "passive"))
    )
    (net (code "80") (name "Net-(U6-MUXOUT)") (class "Default")
      (node (ref "R32") (pin "1") (pinfunction "1_1") (pintype "passive"))
      (node (ref "U6") (pin "18") (pinfunction "MUXOUT_18") (pintype "passive"))
    )
    (net (code "81") (name "Net-(U12-PB6_(XTAL1{slash}TOSC1))") (class "Default")
      (node (ref "C22") (pin "2") (pinfunction "2_2") (pintype "passive"))
      (node (ref "U12") (pin "7") (pinfunction "PB6_(XTAL1/TOSC1)_7") (pintype "bidirectional"))
      (node (ref "X1") (pin "1") (pinfunction "OSC1_1") (pintype "passive"))
    )
    (net (code "82") (name "Net-(U12-PB7_(XTAL2{slash}TOSC2))") (class "Default")
      (node (ref "C23") (pin "2") (pinfunction "2_2") (pintype "passive"))
      (node (ref "U12") (pin "8") (pinfunction "PB7_(XTAL2/TOSC2)_8") (pintype "bidirectional"))
      (node (ref "X1") (pin "2") (pinfunction "OSC2_2") (pintype "passive"))
    )
    (net (code "83") (name "Net-(U14-EN)") (class "Default")
      (node (ref "C28") (pin "2") (pinfunction "2_2") (pintype "passive"))
      (node (ref "R22") (pin "2") (pinfunction "2_2") (pintype "passive"))
      (node (ref "U14") (pin "7") (pinfunction "Vref2_7") (pintype "passive"))
      (node (ref "U14") (pin "8") (pinfunction "EN_8") (pintype "passive"))
    )
    (net (code "84") (name "VREF") (class "Default")
      (node (ref "C15") (pin "2") (pinfunction "2_2") (pintype "passive"))
      (node (ref "C21") (pin "2") (pinfunction "2_2") (pintype "passive"))
      (node (ref "C26") (pin "1") (pinfunction "1_1") (pintype "passive"))
      (node (ref "C9") (pin "2") (pinfunction "2_2") (pintype "passive"))
      (node (ref "U10") (pin "5") (pinfunction "OUT_5") (pintype "power_in"))
      (node (ref "U12") (pin "20") (pinfunction "AREF_20") (pintype "passive"))
      (node (ref "U3") (pin "16") (pinfunction "V_REF_16") (pintype "passive"))
      (node (ref "U6") (pin "16") (pinfunction "V_REF_16") (pintype "passive"))
    )
    (net (code "85") (name "unconnected-(U3-N{slash}C-Pad12)") (class "Default")
      (node (ref "U3") (pin "12") (pinfunction "N/C_12") (pintype "passive+no_connect"))
    )
    (net (code "86") (name "unconnected-(U3-N{slash}C-Pad13)") (class "Default")
      (node (ref "U3") (pin "13") (pinfunction "N/C_13") (pintype "passive+no_connect"))
    )
    (net (code "87") (name "unconnected-(U4-CH7-Pad23)") (class "Default")
      (node (ref "U4") (pin "23") (pinfunction "CH7_23") (pintype "passive+no_connect"))
    )
    (net (code "88") (name "unconnected-(U6-N{slash}C-Pad12)") (class "Default")
      (node (ref "U6") (pin "12") (pinfunction "N/C_12") (pintype "passive+no_connect"))
    )
    (net (code "89") (name "unconnected-(U6-N{slash}C-Pad13)") (class "Default")
      (node (ref "U6") (pin "13") (pinfunction "N/C_13") (pintype "passive+no_connect"))
    )
    (net (code "90") (name "unconnected-(U7-V_OUTD-Pad5)") (class "Default")
      (node (ref "U7") (pin "5") (pinfunction "V_OUTD_5") (pintype "passive+no_connect"))
    )
    (net (code "91") (name "unconnected-(U7-V_OUTE-Pad12)") (class "Default")
      (node (ref "U7") (pin "12") (pinfunction "V_OUTE_12") (pintype "passive+no_connect"))
    )
    (net (code "92") (name "unconnected-(U10-REF-Pad1)") (class "Default")
      (node (ref "U10") (pin "1") (pinfunction "REF_1") (pintype "passive+no_connect"))
    )
    (net (code "93") (name "unconnected-(U12-ADC6-Pad19)") (class "Default")
      (node (ref "U12") (pin "19") (pinfunction "ADC6_19") (pintype "input+no_connect"))
    )
    (net (code "94") (name "unconnected-(U12-ADC7-Pad22)") (class "Default")
      (node (ref "U12") (pin "22") (pinfunction "ADC7_22") (pintype "input+no_connect"))
    )
    (net (code "95") (name "unconnected-(U12-PC0_(ADC0)-Pad23)") (class "Default")
      (node (ref "U12") (pin "23") (pinfunction "PC0_(ADC0)_23") (pintype "bidirectional+no_connect"))
    )
    (net (code "96") (name "unconnected-(U12-PC1_(ADC1)-Pad24)") (class "Default")
      (node (ref "U12") (pin "24") (pinfunction "PC1_(ADC1)_24") (pintype "bidirectional+no_connect"))
    )
    (net (code "97") (name "unconnected-(U12-PC2_(ADC2)-Pad25)") (class "Default")
      (node (ref "U12") (pin "25") (pinfunction "PC2_(ADC2)_25") (pintype "bidirectional+no_connect"))
    )
    (net (code "98") (name "unconnected-(U12-PC3_(ADC3)-Pad26)") (class "Default")
      (node (ref "U12") (pin "26") (pinfunction "PC3_(ADC3)_26") (pintype "bidirectional+no_connect"))
    )
  )
)
